# design.net
KiCad netlist of a schematic drawn in Altium Designer
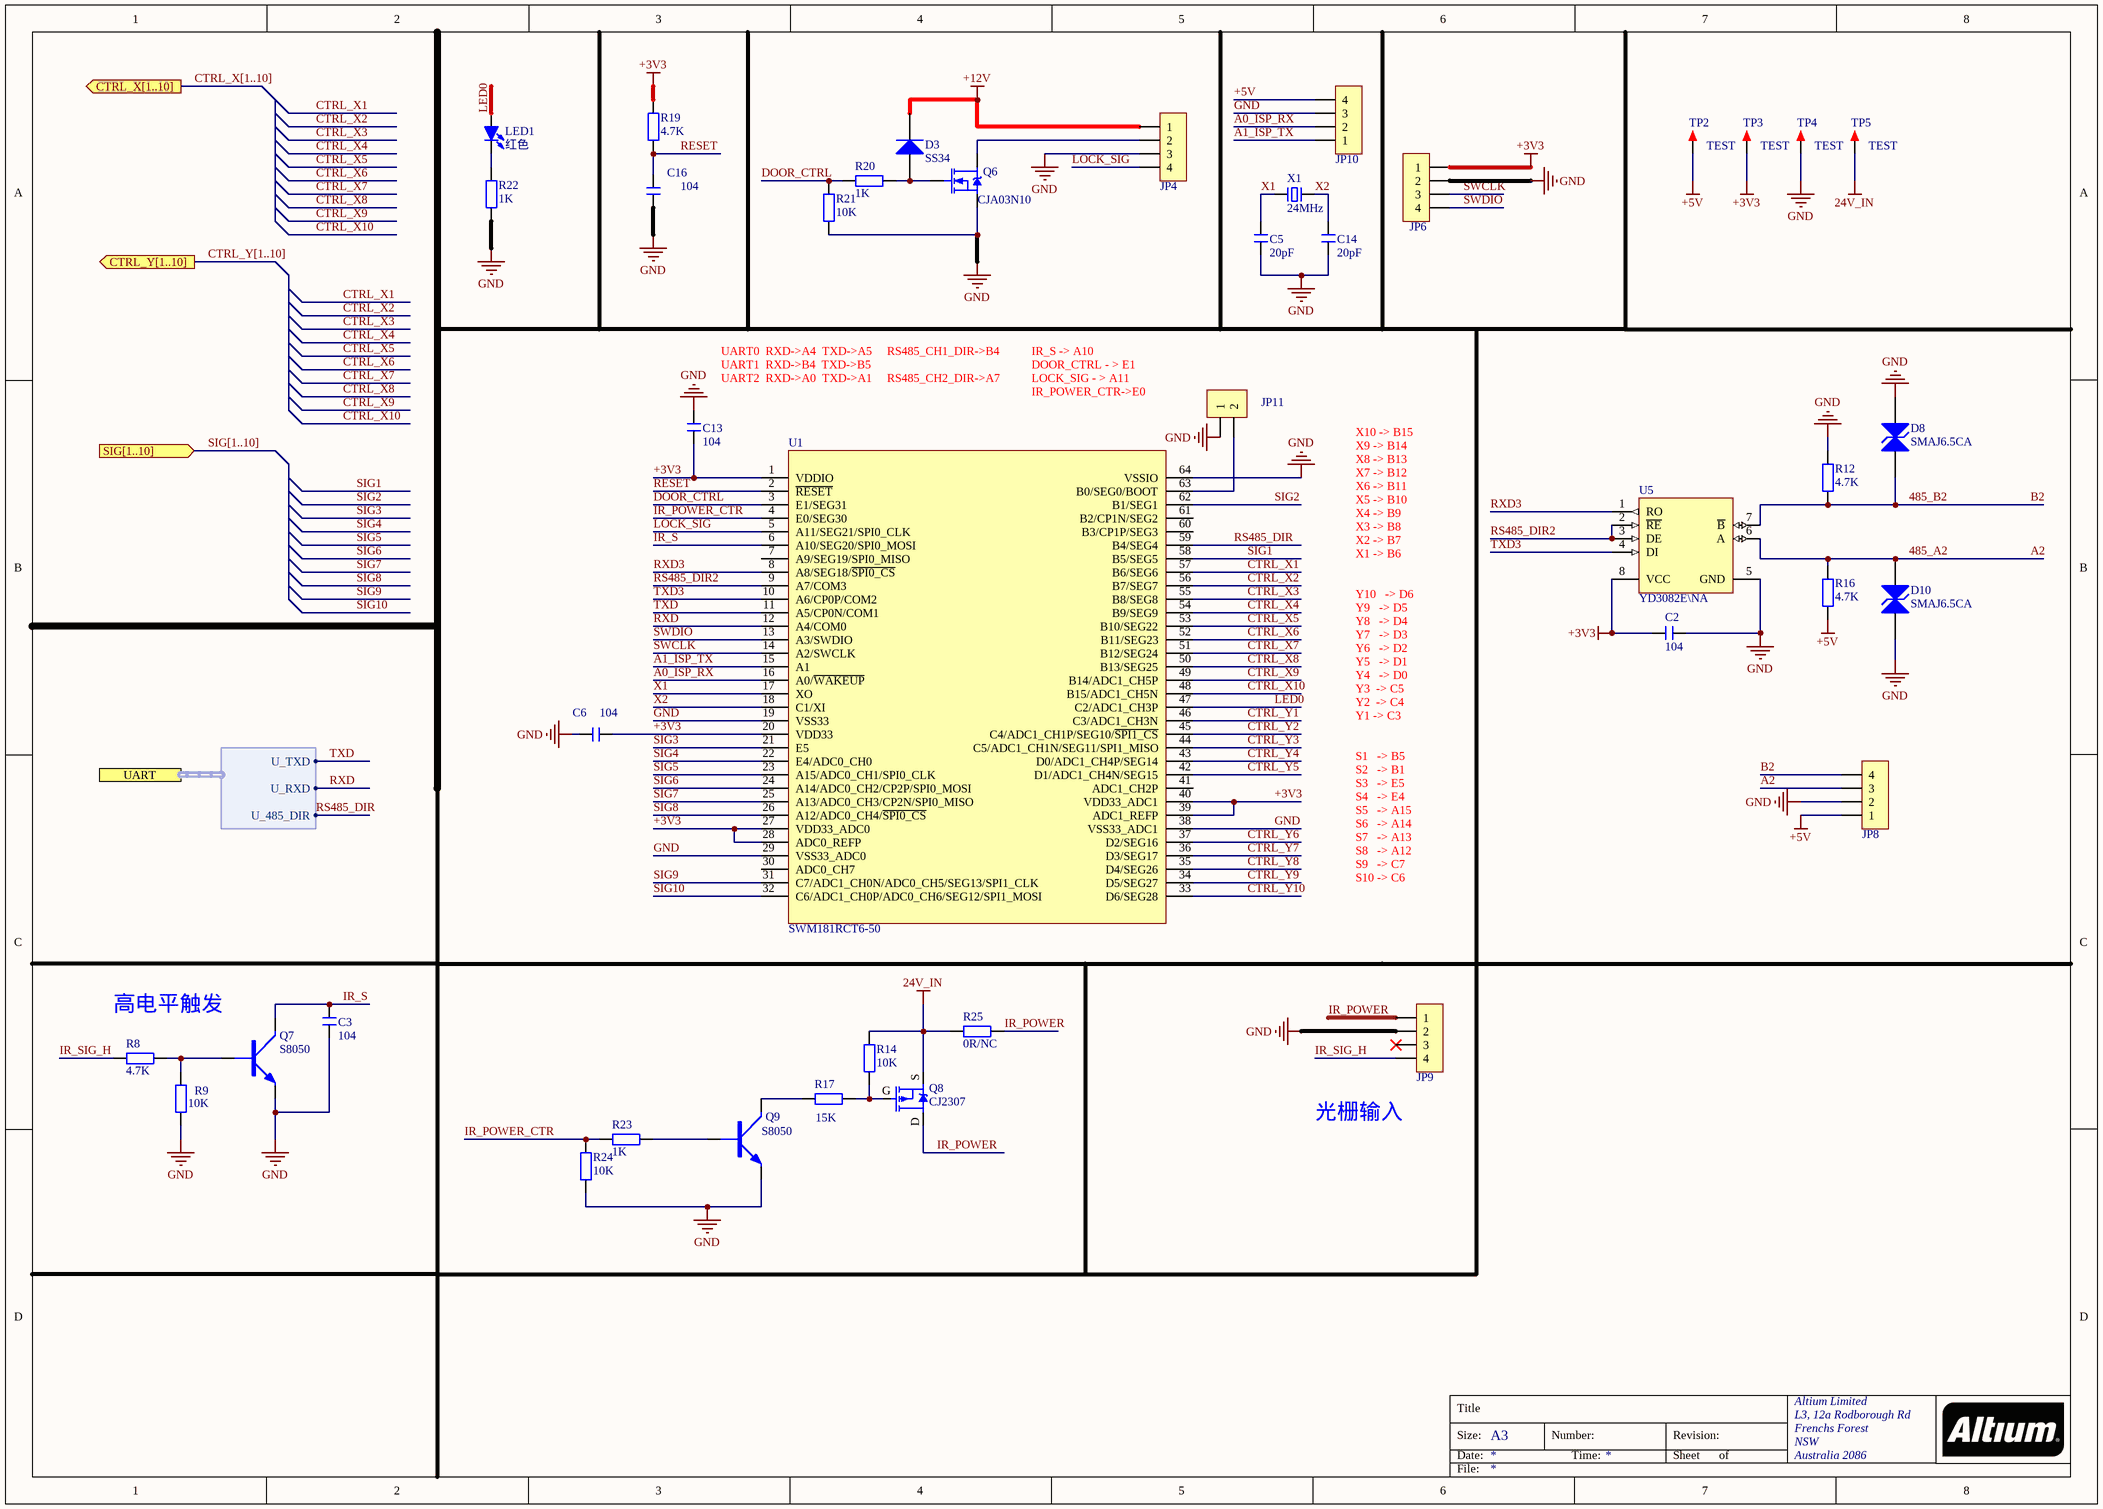
[diagram p0: 主控制器.SchDoc]

(export (version "E")
  (design (tool "Eeschema 10.0.6"))
  (components
    (comp (ref "C2")
      (value "104")
      (footprint "C 0603")
      (description "无极性贴片电容")
      (fields (field (name "版权归属") "源创客"))
      (libsource (lib "源创客") (part "C"))
    )
    (comp (ref "C3")
      (value "104")
      (footprint "C 0603")
      (description "无极性贴片电容")
      (fields (field (name "版权归属") "源创客"))
      (libsource (lib "源创客") (part "C"))
    )
    (comp (ref "C5")
      (value "20pF")
      (footprint "C 0603")
      (description "无极性贴片电容")
      (fields (field (name "版权归属") "源创客"))
      (libsource (lib "源创客") (part "C"))
    )
    (comp (ref "C6")
      (value "104")
      (footprint "C 0603")
      (description "无极性贴片电容")
      (fields (field (name "版权归属") "源创客"))
      (libsource (lib "源创客") (part "C"))
    )
    (comp (ref "C13")
      (value "104")
      (footprint "C 0603")
      (description "无极性贴片电容")
      (fields (field (name "版权归属") "源创客"))
      (libsource (lib "源创客") (part "C"))
    )
    (comp (ref "C14")
      (value "20pF")
      (footprint "C 0603")
      (description "无极性贴片电容")
      (fields (field (name "版权归属") "源创客"))
      (libsource (lib "源创客") (part "C"))
    )
    (comp (ref "C16")
      (value "104")
      (footprint "C 0603")
      (description "无极性贴片电容")
      (fields (field (name "版权归属") "源创客"))
      (libsource (lib "源创客") (part "C"))
    )
    (comp (ref "D3")
      (value "SS34")
      (footprint "SMA(DO-214AC)_S1")
      (description "二极管")
      (libsource (lib "Miscellaneous Devices LC") (part "SMA(DO-214AC) SS54"))
    )
    (comp (ref "D8")
      (value "SMAJ6.5CA")
      (footprint "SMA(DO-214AC)_S1")
      (description "TVS")
      (libsource (lib "Miscellaneous Devices LC") (part "SMB/DO-214AA P6SMB6.8CA"))
    )
    (comp (ref "D10")
      (value "SMAJ6.5CA")
      (footprint "SMA(DO-214AC)_S1")
      (description "TVS")
      (libsource (lib "Miscellaneous Devices LC") (part "SMB/DO-214AA P6SMB6.8CA"))
    )
    (comp (ref "JP4")
      (value "XH-2.54-4P")
      (footprint "XH2.54-4P")
      (description "4P接插件")
      (fields (field (name "版权归属") "源创客"))
      (libsource (lib "源创客") (part "Header 4"))
    )
    (comp (ref "JP6")
      (value "HDR-1X4")
      (footprint "HDR-1X4")
      (description "4P接插件")
      (fields (field (name "版权归属") "源创客"))
      (libsource (lib "") (part "Header 4_1"))
    )
    (comp (ref "JP8")
      (value "XH-2.54-4P")
      (footprint "XH2.54-4P")
      (description "4P接插件")
      (fields (field (name "版权归属") "源创客"))
      (libsource (lib "") (part "Header 4_2"))
    )
    (comp (ref "JP9")
      (value "HDR-1X4")
      (footprint "XH2.54-4P")
      (description "4P接插件")
      (fields (field (name "版权归属") "源创客"))
      (libsource (lib "源创客") (part "Header 4"))
    )
    (comp (ref "JP10")
      (value "XH-2.54-4P")
      (footprint "XH2.54-4P")
      (description "4P接插件")
      (fields (field (name "版权归属") "源创客"))
      (libsource (lib "") (part "Header 4_2"))
    )
    (comp (ref "JP11")
      (value "HDR-1X2")
      (footprint "HDR-1X2")
      (description "2P接插件")
      (fields (field (name "版权归属") "源创客"))
      (libsource (lib "源创客") (part "Header 2"))
    )
    (comp (ref "LED1")
      (value "红色")
      (footprint "LED 0603G")
      (description "贴片LED")
      (fields (field (name "版权归属") "源创客"))
      (libsource (lib "源创客") (part "LED-SMD"))
    )
    (comp (ref "Q6")
      (value "CJA03N10")
      (footprint "LC-SOT-89(SOT-89-3)")
      (description "N沟道场效应管")
      (libsource (lib "this") (part "CJA03N10"))
    )
    (comp (ref "Q7")
      (value "S8050")
      (footprint "SOT-23")
      (description "NPN三极管")
      (libsource (lib "三极管") (part "NPN"))
    )
    (comp (ref "Q8")
      (value "CJ2307")
      (footprint "SOT23")
      (description "P沟道场效应管")
      (libsource (lib "MOS管") (part "P-MOS"))
    )
    (comp (ref "Q9")
      (value "S8050")
      (footprint "SOT-23")
      (description "NPN三极管")
      (libsource (lib "三极管") (part "NPN"))
    )
    (comp (ref "R8")
      (value "4.7K")
      (footprint "R 0603")
      (description "贴片电阻")
      (fields (field (name "版权归属") "源创客"))
      (libsource (lib "源创客") (part "R"))
    )
    (comp (ref "R9")
      (value "10K")
      (footprint "R 0603")
      (description "贴片电阻")
      (fields (field (name "版权归属") "源创客"))
      (libsource (lib "源创客") (part "R"))
    )
    (comp (ref "R12")
      (value "4.7K")
      (footprint "R 0603")
      (description "贴片电阻")
      (fields (field (name "版权归属") "源创客"))
      (libsource (lib "源创客") (part "R"))
    )
    (comp (ref "R14")
      (value "10K")
      (footprint "R 0603")
      (description "贴片电阻")
      (fields (field (name "版权归属") "源创客"))
      (libsource (lib "源创客") (part "R"))
    )
    (comp (ref "R16")
      (value "4.7K")
      (footprint "R 0603")
      (description "贴片电阻")
      (fields (field (name "版权归属") "源创客"))
      (libsource (lib "源创客") (part "R"))
    )
    (comp (ref "R17")
      (value "15K")
      (footprint "R 0603")
      (description "贴片电阻")
      (fields (field (name "版权归属") "源创客"))
      (libsource (lib "源创客") (part "R"))
    )
    (comp (ref "R19")
      (value "4.7K")
      (footprint "R 0603")
      (description "贴片电阻")
      (fields (field (name "版权归属") "源创客"))
      (libsource (lib "源创客") (part "R"))
    )
    (comp (ref "R20")
      (value "1K")
      (footprint "R 0603")
      (description "贴片电阻")
      (fields (field (name "版权归属") "源创客"))
      (libsource (lib "源创客") (part "R"))
    )
    (comp (ref "R21")
      (value "10K")
      (footprint "R 0603")
      (description "贴片电阻")
      (fields (field (name "版权归属") "源创客"))
      (libsource (lib "源创客") (part "R"))
    )
    (comp (ref "R22")
      (value "1K")
      (footprint "R 0603")
      (description "贴片电阻")
      (fields (field (name "版权归属") "源创客"))
      (libsource (lib "源创客") (part "R"))
    )
    (comp (ref "R23")
      (value "1K")
      (footprint "R 0603")
      (description "贴片电阻")
      (fields (field (name "版权归属") "源创客"))
      (libsource (lib "源创客") (part "R"))
    )
    (comp (ref "R24")
      (value "10K")
      (footprint "R 0603")
      (description "贴片电阻")
      (fields (field (name "版权归属") "源创客"))
      (libsource (lib "源创客") (part "R"))
    )
    (comp (ref "R25")
      (value "0R/NC")
      (footprint "R 0603")
      (description "贴片电阻")
      (fields (field (name "版权归属") "源创客"))
      (libsource (lib "源创客") (part "R"))
    )
    (comp (ref "TP2")
      (value "TEST")
      (footprint "TEST 1")
      (description "测试点")
      (fields (field (name "版权归属") "源创客"))
      (libsource (lib "源创客") (part "TEST"))
    )
    (comp (ref "TP3")
      (value "TEST")
      (footprint "TEST 1")
      (description "测试点")
      (fields (field (name "版权归属") "源创客"))
      (libsource (lib "源创客") (part "TEST"))
    )
    (comp (ref "TP4")
      (value "TEST")
      (footprint "TEST 1")
      (description "测试点")
      (fields (field (name "版权归属") "源创客"))
      (libsource (lib "源创客") (part "TEST"))
    )
    (comp (ref "TP5")
      (value "TEST")
      (footprint "TEST 1")
      (description "测试点")
      (fields (field (name "版权归属") "源创客"))
      (libsource (lib "源创客") (part "TEST"))
    )
    (comp (ref "U1")
      (value "SWM181RCT6-50")
      (footprint "LC-LQFP-64_10x10x05P")
      (description "微控制器, Cortex-M0系列, AA-00")
      (libsource (lib "SW_MCU_Library_20180827") (part "SWM181RCT6-50"))
    )
    (comp (ref "U5")
      (value "YD3082~{E}NA")
      (footprint "SOIC-8_150mil")
      (description "RS-485/RS-422")
      (libsource (lib "Miscellaneous Devices LC") (part "SP485EEN-L/TR"))
    )
    (comp (ref "X1")
      (value "24MHz")
      (footprint "XTAL-49S SMD")
      (description "2脚晶振")
      (fields (field (name "版权归属") "源创客"))
      (libsource (lib "源创客") (part "XTAL-2"))
    )
  )
  (nets
    (net (code "2") (name "+3V3") (class "Default")
      (node (ref "C13") (pin "2") (pinfunction "2_2") (pintype "passive"))
      (node (ref "C2") (pin "1") (pinfunction "1_1") (pintype "passive"))
      (node (ref "C6") (pin "2") (pinfunction "2_2") (pintype "passive"))
      (node (ref "JP6") (pin "1") (pinfunction "1_1") (pintype "passive"))
      (node (ref "R19") (pin "2") (pinfunction "2_2") (pintype "passive"))
      (node (ref "TP3") (pin "1") (pinfunction "1_1") (pintype "passive"))
      (node (ref "U1") (pin "1") (pinfunction "VDDIO_1") (pintype "passive"))
      (node (ref "U1") (pin "20") (pinfunction "VDD33_20") (pintype "passive"))
      (node (ref "U1") (pin "27") (pinfunction "VDD33_ADC0_27") (pintype "passive"))
      (node (ref "U1") (pin "28") (pinfunction "ADC0_REFP_28") (pintype "passive"))
      (node (ref "U1") (pin "39") (pinfunction "ADC1_REFP_39") (pintype "passive"))
      (node (ref "U1") (pin "40") (pinfunction "VDD33_ADC1_40") (pintype "passive"))
      (node (ref "U5") (pin "8") (pinfunction "VCC_8") (pintype "power_in"))
    )
    (net (code "3") (name "+5V") (class "Default")
      (node (ref "JP10") (pin "4") (pinfunction "4_4") (pintype "passive"))
      (node (ref "JP8") (pin "1") (pinfunction "1_1") (pintype "passive"))
      (node (ref "R16") (pin "1") (pinfunction "1_1") (pintype "passive"))
      (node (ref "TP2") (pin "1") (pinfunction "1_1") (pintype "passive"))
    )
    (net (code "4") (name "+12V") (class "Default")
      (node (ref "D3") (pin "2") (pinfunction "K_2") (pintype "passive"))
      (node (ref "JP4") (pin "1") (pinfunction "1_1") (pintype "passive"))
    )
    (net (code "5") (name "/485_A2") (class "Default")
      (node (ref "D10") (pin "2") (pinfunction "K_2") (pintype "passive"))
      (node (ref "JP8") (pin "3") (pinfunction "3_3") (pintype "passive"))
      (node (ref "R16") (pin "2") (pinfunction "2_2") (pintype "passive"))
      (node (ref "U5") (pin "6") (pinfunction "A_6") (pintype "bidirectional"))
    )
    (net (code "6") (name "/485_B2") (class "Default")
      (node (ref "D8") (pin "2") (pinfunction "K_2") (pintype "passive"))
      (node (ref "JP8") (pin "4") (pinfunction "4_4") (pintype "passive"))
      (node (ref "R12") (pin "1") (pinfunction "1_1") (pintype "passive"))
      (node (ref "U5") (pin "7") (pinfunction "~{B}_7") (pintype "bidirectional"))
    )
    (net (code "7") (name "/A0_ISP_RX") (class "Default")
      (node (ref "JP10") (pin "2") (pinfunction "2_2") (pintype "passive"))
      (node (ref "U1") (pin "16") (pinfunction "A0/~{WAKEUP}_16") (pintype "passive"))
    )
    (net (code "8") (name "/A1_ISP_TX") (class "Default")
      (node (ref "JP10") (pin "1") (pinfunction "1_1") (pintype "passive"))
      (node (ref "U1") (pin "15") (pinfunction "A1_15") (pintype "passive"))
    )
    (net (code "9") (name "/CTRL_X1") (class "Default")
      (node (ref "U1") (pin "57") (pinfunction "B6/SEG6_57") (pintype "passive"))
    )
    (net (code "10") (name "/CTRL_X2") (class "Default")
      (node (ref "U1") (pin "56") (pinfunction "B7/SEG7_56") (pintype "passive"))
    )
    (net (code "11") (name "/CTRL_X3") (class "Default")
      (node (ref "U1") (pin "55") (pinfunction "B8/SEG8_55") (pintype "passive"))
    )
    (net (code "12") (name "/CTRL_X4") (class "Default")
      (node (ref "U1") (pin "54") (pinfunction "B9/SEG9_54") (pintype "passive"))
    )
    (net (code "13") (name "/CTRL_X5") (class "Default")
      (node (ref "U1") (pin "53") (pinfunction "B10/SEG22_53") (pintype "passive"))
    )
    (net (code "14") (name "/CTRL_X6") (class "Default")
      (node (ref "U1") (pin "52") (pinfunction "B11/SEG23_52") (pintype "passive"))
    )
    (net (code "15") (name "/CTRL_X7") (class "Default")
      (node (ref "U1") (pin "51") (pinfunction "B12/SEG24_51") (pintype "passive"))
    )
    (net (code "16") (name "/CTRL_X8") (class "Default")
      (node (ref "U1") (pin "50") (pinfunction "B13/SEG25_50") (pintype "passive"))
    )
    (net (code "17") (name "/CTRL_X9") (class "Default")
      (node (ref "U1") (pin "49") (pinfunction "B14/ADC1_CH5P_49") (pintype "passive"))
    )
    (net (code "18") (name "/CTRL_X10") (class "Default")
      (node (ref "U1") (pin "48") (pinfunction "B15/ADC1_CH5N_48") (pintype "passive"))
    )
    (net (code "20") (name "/CTRL_Y1") (class "Default")
      (node (ref "U1") (pin "46") (pinfunction "C3/ADC1_CH3N_46") (pintype "passive"))
    )
    (net (code "21") (name "/CTRL_Y2") (class "Default")
      (node (ref "U1") (pin "45") (pinfunction "C4/ADC1_CH1P/SEG10/~{SPI1_CS}_45") (pintype "passive"))
    )
    (net (code "22") (name "/CTRL_Y3") (class "Default")
      (node (ref "U1") (pin "44") (pinfunction "C5/ADC1_CH1N/SEG11/SPI1_MISO_44") (pintype "passive"))
    )
    (net (code "23") (name "/CTRL_Y4") (class "Default")
      (node (ref "U1") (pin "43") (pinfunction "D0/ADC1_CH4P/SEG14_43") (pintype "passive"))
    )
    (net (code "24") (name "/CTRL_Y5") (class "Default")
      (node (ref "U1") (pin "42") (pinfunction "D1/ADC1_CH4N/SEG15_42") (pintype "passive"))
    )
    (net (code "25") (name "/CTRL_Y6") (class "Default")
      (node (ref "U1") (pin "37") (pinfunction "D2/SEG16_37") (pintype "passive"))
    )
    (net (code "26") (name "/CTRL_Y7") (class "Default")
      (node (ref "U1") (pin "36") (pinfunction "D3/SEG17_36") (pintype "passive"))
    )
    (net (code "27") (name "/CTRL_Y8") (class "Default")
      (node (ref "U1") (pin "35") (pinfunction "D4/SEG26_35") (pintype "passive"))
    )
    (net (code "28") (name "/CTRL_Y9") (class "Default")
      (node (ref "U1") (pin "34") (pinfunction "D5/SEG27_34") (pintype "passive"))
    )
    (net (code "29") (name "/CTRL_Y10") (class "Default")
      (node (ref "U1") (pin "33") (pinfunction "D6/SEG28_33") (pintype "passive"))
    )
    (net (code "31") (name "/DOOR_CTRL") (class "Default")
      (node (ref "R20") (pin "1") (pinfunction "1_1") (pintype "passive"))
      (node (ref "R21") (pin "1") (pinfunction "1_1") (pintype "passive"))
      (node (ref "U1") (pin "3") (pinfunction "E1/SEG31_3") (pintype "passive"))
    )
    (net (code "32") (name "/IR_POWER") (class "Default")
      (node (ref "JP9") (pin "1") (pinfunction "1_1") (pintype "passive"))
      (node (ref "Q8") (pin "D") (pinfunction "D_D") (pintype "passive"))
      (node (ref "R25") (pin "1") (pinfunction "1_1") (pintype "passive"))
    )
    (net (code "33") (name "/IR_POWER_CTR") (class "Default")
      (node (ref "R23") (pin "1") (pinfunction "1_1") (pintype "passive"))
      (node (ref "R24") (pin "1") (pinfunction "1_1") (pintype "passive"))
      (node (ref "U1") (pin "4") (pinfunction "E0/SEG30_4") (pintype "passive"))
    )
    (net (code "34") (name "/IR_S") (class "Default")
      (node (ref "C3") (pin "2") (pinfunction "2_2") (pintype "passive"))
      (node (ref "Q7") (pin "C") (pinfunction "C_C") (pintype "passive"))
      (node (ref "U1") (pin "6") (pinfunction "A10/SEG20/SPI0_MOSI_6") (pintype "passive"))
    )
    (net (code "35") (name "/IR_SIG_H") (class "Default")
      (node (ref "JP9") (pin "4") (pinfunction "4_4") (pintype "passive"))
      (node (ref "R8") (pin "2") (pinfunction "2_2") (pintype "passive"))
    )
    (net (code "36") (name "/LED0") (class "Default")
      (node (ref "LED1") (pin "1") (pinfunction "A_1") (pintype "passive"))
      (node (ref "U1") (pin "47") (pinfunction "C2/ADC1_CH3P_47") (pintype "passive"))
    )
    (net (code "37") (name "/LOCK_SIG") (class "Default")
      (node (ref "JP4") (pin "4") (pinfunction "4_4") (pintype "passive"))
      (node (ref "U1") (pin "5") (pinfunction "A11/SEG21/SPI0_CLK_5") (pintype "passive"))
    )
    (net (code "38") (name "/RESET") (class "Default")
      (node (ref "C16") (pin "1") (pinfunction "1_1") (pintype "passive"))
      (node (ref "R19") (pin "1") (pinfunction "1_1") (pintype "passive"))
      (node (ref "U1") (pin "2") (pinfunction "~{RESET}_2") (pintype "passive"))
    )
    (net (code "39") (name "/RS485_DIR") (class "Default")
      (node (ref "U1") (pin "59") (pinfunction "B4/SEG4_59") (pintype "passive"))
    )
    (net (code "40") (name "/RS485_DIR2") (class "Default")
      (node (ref "U1") (pin "9") (pinfunction "A7/COM3_9") (pintype "passive"))
      (node (ref "U5") (pin "2") (pinfunction "~{RE}_2") (pintype "input"))
      (node (ref "U5") (pin "3") (pinfunction "DE_3") (pintype "input"))
    )
    (net (code "41") (name "/RXD") (class "Default")
      (node (ref "U1") (pin "12") (pinfunction "A4/COM0_12") (pintype "passive"))
    )
    (net (code "42") (name "/RXD3") (class "Default")
      (node (ref "U1") (pin "8") (pinfunction "A8/SEG18/~{SPI0_CS}_8") (pintype "passive"))
      (node (ref "U5") (pin "1") (pinfunction "RO_1") (pintype "output"))
    )
    (net (code "43") (name "/SIG1") (class "Default")
      (node (ref "U1") (pin "58") (pinfunction "B5/SEG5_58") (pintype "passive"))
    )
    (net (code "44") (name "/SIG2") (class "Default")
      (node (ref "U1") (pin "62") (pinfunction "B1/SEG1_62") (pintype "passive"))
    )
    (net (code "45") (name "/SIG3") (class "Default")
      (node (ref "U1") (pin "21") (pinfunction "E5_21") (pintype "passive"))
    )
    (net (code "46") (name "/SIG4") (class "Default")
      (node (ref "U1") (pin "22") (pinfunction "E4/ADC0_CH0_22") (pintype "passive"))
    )
    (net (code "47") (name "/SIG5") (class "Default")
      (node (ref "U1") (pin "23") (pinfunction "A15/ADC0_CH1/SPI0_CLK_23") (pintype "passive"))
    )
    (net (code "48") (name "/SIG6") (class "Default")
      (node (ref "U1") (pin "24") (pinfunction "A14/ADC0_CH2/CP2P/SPI0_MOSI_24") (pintype "passive"))
    )
    (net (code "49") (name "/SIG7") (class "Default")
      (node (ref "U1") (pin "25") (pinfunction "A13/ADC0_CH3/CP2N/SPI0_MISO_25") (pintype "passive"))
    )
    (net (code "50") (name "/SIG8") (class "Default")
      (node (ref "U1") (pin "26") (pinfunction "A12/ADC0_CH4/~{SPI0_CS}_26") (pintype "passive"))
    )
    (net (code "51") (name "/SIG9") (class "Default")
      (node (ref "U1") (pin "31") (pinfunction "C7/ADC1_CH0N/ADC0_CH5/SEG13/SPI1_CLK_31") (pintype "passive"))
    )
    (net (code "52") (name "/SIG10") (class "Default")
      (node (ref "U1") (pin "32") (pinfunction "C6/ADC1_CH0P/ADC0_CH6/SEG12/SPI1_MOSI_32") (pintype "passive"))
    )
    (net (code "54") (name "/SWCLK") (class "Default")
      (node (ref "JP6") (pin "3") (pinfunction "3_3") (pintype "passive"))
      (node (ref "U1") (pin "14") (pinfunction "A2/SWCLK_14") (pintype "passive"))
    )
    (net (code "55") (name "/SWDIO") (class "Default")
      (node (ref "JP6") (pin "4") (pinfunction "4_4") (pintype "passive"))
      (node (ref "U1") (pin "13") (pinfunction "A3/SWDIO_13") (pintype "passive"))
    )
    (net (code "56") (name "/TXD") (class "Default")
      (node (ref "U1") (pin "11") (pinfunction "A5/CP0N/COM1_11") (pintype "passive"))
    )
    (net (code "57") (name "/TXD3") (class "Default")
      (node (ref "U1") (pin "10") (pinfunction "A6/CP0P/COM2_10") (pintype "passive"))
      (node (ref "U5") (pin "4") (pinfunction "DI_4") (pintype "input"))
    )
    (net (code "58") (name "/X1") (class "Default")
      (node (ref "C5") (pin "2") (pinfunction "2_2") (pintype "passive"))
      (node (ref "U1") (pin "17") (pinfunction "XO_17") (pintype "passive"))
      (node (ref "X1") (pin "1") (pinfunction "1_1") (pintype "passive"))
    )
    (net (code "59") (name "/X2") (class "Default")
      (node (ref "C14") (pin "2") (pinfunction "2_2") (pintype "passive"))
      (node (ref "U1") (pin "18") (pinfunction "C1/XI_18") (pintype "passive"))
      (node (ref "X1") (pin "2") (pinfunction "2_2") (pintype "passive"))
    )
    (net (code "61") (name "24V_IN") (class "Default")
      (node (ref "Q8") (pin "S") (pinfunction "S_S") (pintype "passive"))
      (node (ref "R14") (pin "2") (pinfunction "2_2") (pintype "passive"))
      (node (ref "R25") (pin "2") (pinfunction "2_2") (pintype "passive"))
      (node (ref "TP5") (pin "1") (pinfunction "1_1") (pintype "passive"))
    )
    (net (code "62") (name "GND") (class "Default")
      (node (ref "C13") (pin "1") (pinfunction "1_1") (pintype "passive"))
      (node (ref "C14") (pin "1") (pinfunction "1_1") (pintype "passive"))
      (node (ref "C16") (pin "2") (pinfunction "2_2") (pintype "passive"))
      (node (ref "C2") (pin "2") (pinfunction "2_2") (pintype "passive"))
      (node (ref "C3") (pin "1") (pinfunction "1_1") (pintype "passive"))
      (node (ref "C5") (pin "1") (pinfunction "1_1") (pintype "passive"))
      (node (ref "C6") (pin "1") (pinfunction "1_1") (pintype "passive"))
      (node (ref "D10") (pin "1") (pinfunction "A_1") (pintype "passive"))
      (node (ref "D8") (pin "1") (pinfunction "A_1") (pintype "passive"))
      (node (ref "JP10") (pin "3") (pinfunction "3_3") (pintype "passive"))
      (node (ref "JP11") (pin "1") (pinfunction "1_1") (pintype "passive"))
      (node (ref "JP4") (pin "3") (pinfunction "3_3") (pintype "passive"))
      (node (ref "JP6") (pin "2") (pinfunction "2_2") (pintype "passive"))
      (node (ref "JP8") (pin "2") (pinfunction "2_2") (pintype "passive"))
      (node (ref "JP9") (pin "2") (pinfunction "2_2") (pintype "passive"))
      (node (ref "Q6") (pin "3") (pinfunction "S_3") (pintype "passive"))
      (node (ref "Q7") (pin "E") (pinfunction "E_E") (pintype "passive"))
      (node (ref "Q9") (pin "E") (pinfunction "E_E") (pintype "passive"))
      (node (ref "R12") (pin "2") (pinfunction "2_2") (pintype "passive"))
      (node (ref "R21") (pin "2") (pinfunction "2_2") (pintype "passive"))
      (node (ref "R22") (pin "1") (pinfunction "1_1") (pintype "passive"))
      (node (ref "R24") (pin "2") (pinfunction "2_2") (pintype "passive"))
      (node (ref "R9") (pin "1") (pinfunction "1_1") (pintype "passive"))
      (node (ref "TP4") (pin "1") (pinfunction "1_1") (pintype "passive"))
      (node (ref "U1") (pin "19") (pinfunction "VSS33_19") (pintype "passive"))
      (node (ref "U1") (pin "29") (pinfunction "VSS33_ADC0_29") (pintype "passive"))
      (node (ref "U1") (pin "38") (pinfunction "VSS33_ADC1_38") (pintype "passive"))
      (node (ref "U1") (pin "64") (pinfunction "VSSIO_64") (pintype "passive"))
      (node (ref "U5") (pin "5") (pinfunction "GND_5") (pintype "power_in"))
    )
    (net (code "63") (name "Net-(D3-A)") (class "Default")
      (node (ref "D3") (pin "1") (pinfunction "A_1") (pintype "passive"))
      (node (ref "Q6") (pin "1") (pinfunction "G_1") (pintype "passive"))
      (node (ref "R20") (pin "2") (pinfunction "2_2") (pintype "passive"))
    )
    (net (code "64") (name "Net-(LED1-K)") (class "Default")
      (node (ref "LED1") (pin "2") (pinfunction "K_2") (pintype "passive"))
      (node (ref "R22") (pin "2") (pinfunction "2_2") (pintype "passive"))
    )
    (net (code "65") (name "Net-(Q6-D)") (class "Default")
      (node (ref "JP4") (pin "2") (pinfunction "2_2") (pintype "passive"))
      (node (ref "Q6") (pin "2") (pinfunction "D_2") (pintype "passive"))
    )
    (net (code "66") (name "Net-(Q7-PadB)") (class "Default")
      (node (ref "Q7") (pin "B") (pinfunction "B_B") (pintype "passive"))
      (node (ref "R8") (pin "1") (pinfunction "1_1") (pintype "passive"))
      (node (ref "R9") (pin "2") (pinfunction "2_2") (pintype "passive"))
    )
    (net (code "67") (name "Net-(Q8-PadG)") (class "Default")
      (node (ref "Q8") (pin "G") (pinfunction "G_G") (pintype "passive"))
      (node (ref "R14") (pin "1") (pinfunction "1_1") (pintype "passive"))
      (node (ref "R17") (pin "1") (pinfunction "1_1") (pintype "passive"))
    )
    (net (code "68") (name "Net-(Q9-PadB)") (class "Default")
      (node (ref "Q9") (pin "B") (pinfunction "B_B") (pintype "passive"))
      (node (ref "R23") (pin "2") (pinfunction "2_2") (pintype "passive"))
    )
    (net (code "69") (name "Net-(Q9-PadC)") (class "Default")
      (node (ref "Q9") (pin "C") (pinfunction "C_C") (pintype "passive"))
      (node (ref "R17") (pin "2") (pinfunction "2_2") (pintype "passive"))
    )
    (net (code "70") (name "Net-(U1-B0{slash}SEG0{slash}BOOT)") (class "Default")
      (node (ref "JP11") (pin "2") (pinfunction "2_2") (pintype "passive"))
      (node (ref "U1") (pin "63") (pinfunction "B0/SEG0/BOOT_63") (pintype "passive"))
    )
    (net (code "71") (name "unconnected-(JP9-Pad3)") (class "Default")
      (node (ref "JP9") (pin "3") (pinfunction "3_3") (pintype "passive+no_connect"))
    )
    (net (code "72") (name "unconnected-(U1-A9{slash}SEG19{slash}SPI0_MISO-Pad7)") (class "Default")
      (node (ref "U1") (pin "7") (pinfunction "A9/SEG19/SPI0_MISO_7") (pintype "passive"))
    )
    (net (code "73") (name "unconnected-(U1-ADC0_CH7-Pad30)") (class "Default")
      (node (ref "U1") (pin "30") (pinfunction "ADC0_CH7_30") (pintype "passive"))
    )
    (net (code "74") (name "unconnected-(U1-ADC1_CH2P-Pad41)") (class "Default")
      (node (ref "U1") (pin "41") (pinfunction "ADC1_CH2P_41") (pintype "passive"))
    )
    (net (code "75") (name "unconnected-(U1-B2{slash}CP1N{slash}SEG2-Pad61)") (class "Default")
      (node (ref "U1") (pin "61") (pinfunction "B2/CP1N/SEG2_61") (pintype "passive"))
    )
    (net (code "76") (name "unconnected-(U1-B3{slash}CP1P{slash}SEG3-Pad60)") (class "Default")
      (node (ref "U1") (pin "60") (pinfunction "B3/CP1P/SEG3_60") (pintype "passive"))
    )
  )
)
